# Senior_design_LED_matrix_3_0.net
KiCad netlist of a schematic drawn in Altium Designer
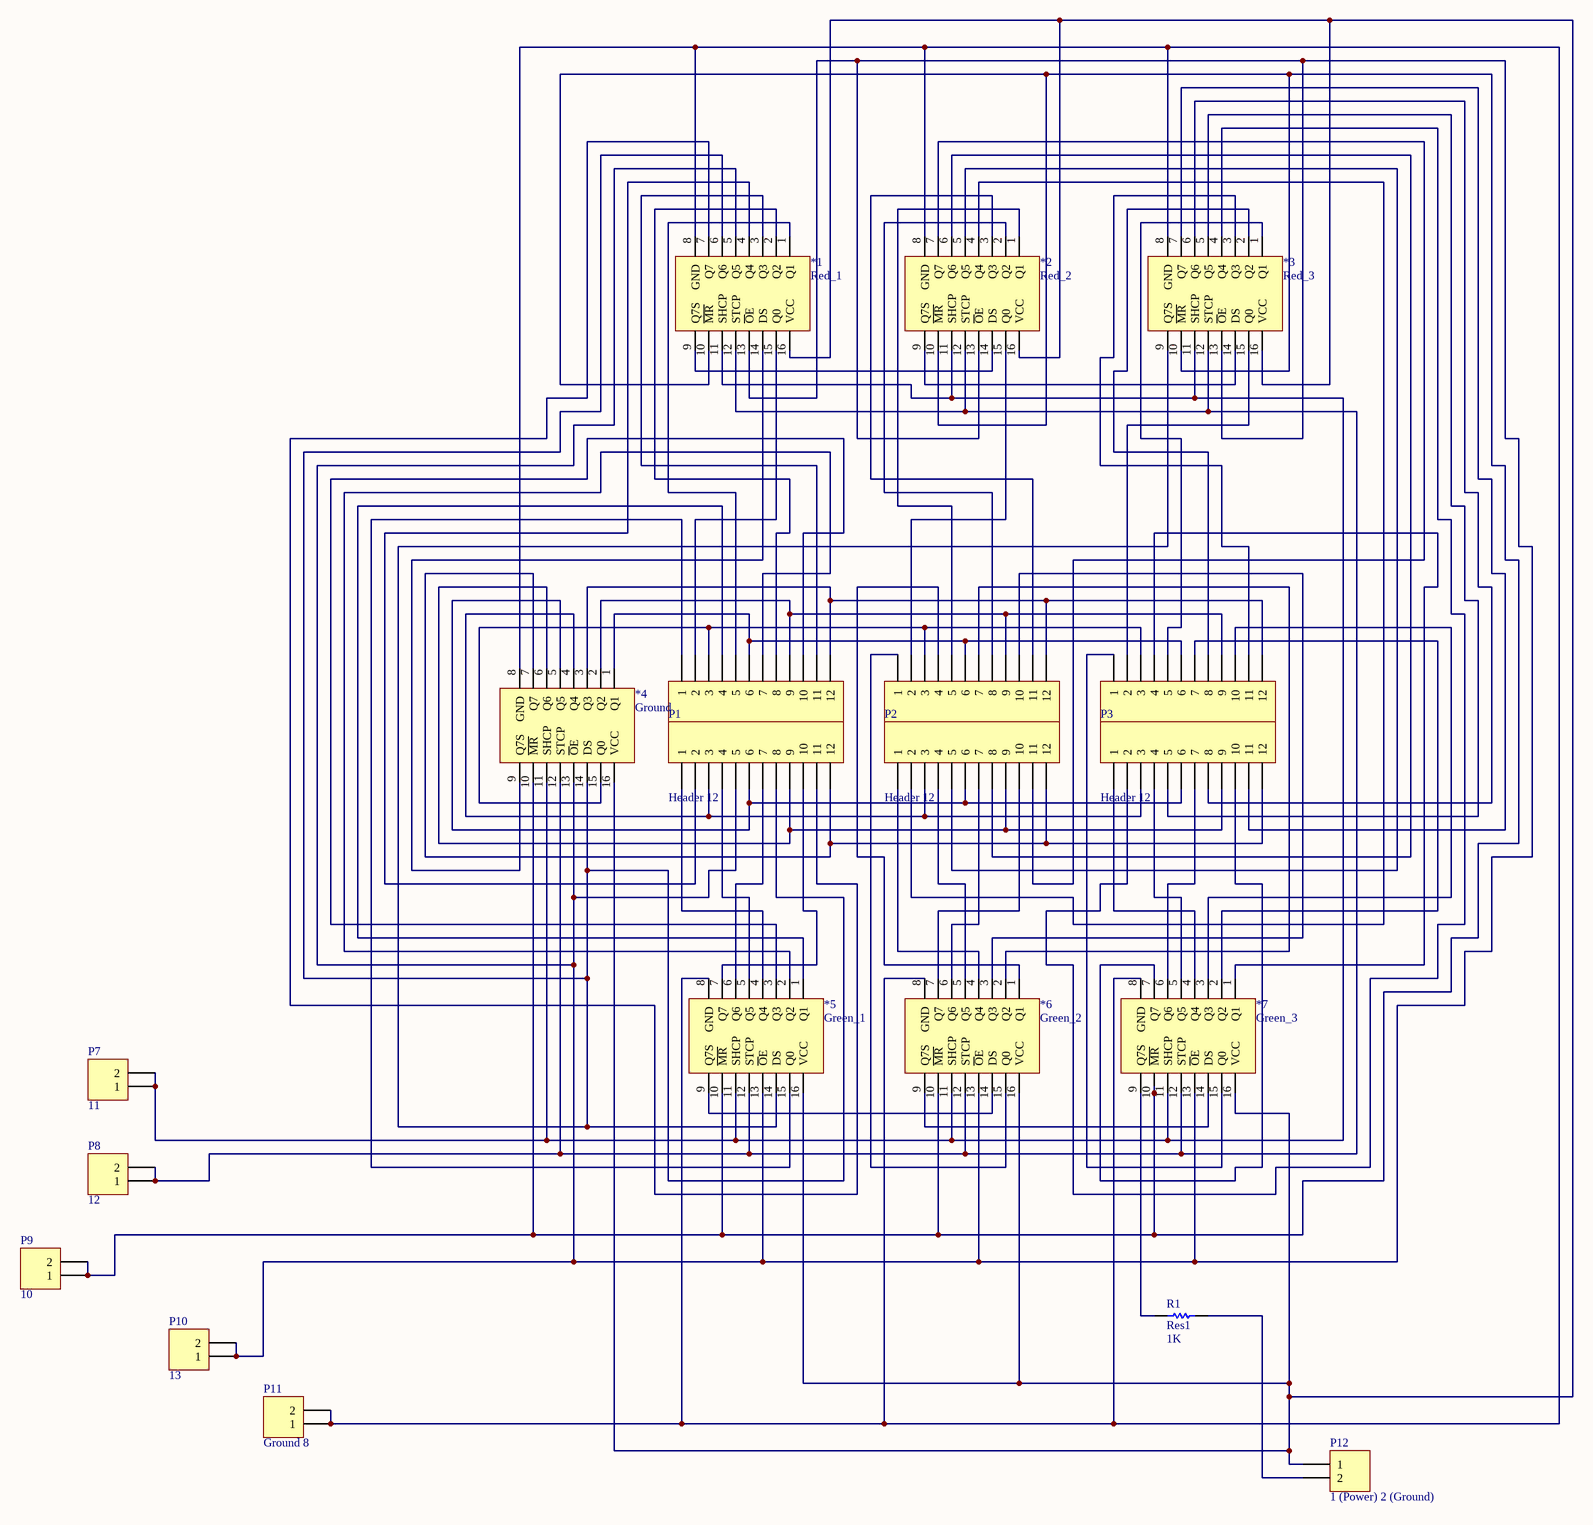
[diagram p0: Senior design LED matrix 3.0.SchDoc]

(export (version "E")
  (design (tool "Eeschema 10.0.6"))
  (components
    (comp (ref "*1") (value "Red_1") (footprint "DIP-16") (libsource (lib "SN74HC595") (part "Component_1")))
    (comp (ref "*2") (value "Red_2") (footprint "DIP-16") (libsource (lib "SN74HC595") (part "Component_1")))
    (comp (ref "*3") (value "Red_3") (footprint "DIP-16") (libsource (lib "SN74HC595") (part "Component_1")))
    (comp (ref "*4") (value "Ground") (footprint "DIP-16") (libsource (lib "SN74HC595") (part "Component_1")))
    (comp (ref "*5")
      (value "Green_1")
      (footprint "DIP-16")
      (libsource (lib "SN74HC595") (part "Component_1"))
    )
    (comp (ref "*6")
      (value "Green_2")
      (footprint "DIP-16")
      (libsource (lib "SN74HC595") (part "Component_1"))
    )
    (comp (ref "*7")
      (value "Green_3")
      (footprint "DIP-16")
      (libsource (lib "SN74HC595") (part "Component_1"))
    )
    (comp (ref "P1")
      (value "Header 12")
      (footprint "HDR1X12")
      (description "Header, 12-Pin")
      (fields (field (name "PUBLISHER") "Altium Limited"))
      (libsource (lib "Miscellaneous Connectors") (part "Header 12"))
    )
    (comp (ref "P2")
      (value "Header 12")
      (footprint "HDR1X12")
      (description "Header, 12-Pin")
      (fields (field (name "PUBLISHER") "Altium Limited"))
      (libsource (lib "Miscellaneous Connectors") (part "Header 12"))
    )
    (comp (ref "P3")
      (value "Header 12")
      (footprint "HDR1X12")
      (description "Header, 12-Pin")
      (fields (field (name "PUBLISHER") "Altium Limited"))
      (libsource (lib "Miscellaneous Connectors") (part "Header 12"))
    )
    (comp (ref "P4")
      (value "Header 12")
      (footprint "HDR1X12")
      (description "Header, 12-Pin")
      (fields (field (name "PUBLISHER") "Altium Limited"))
      (libsource (lib "") (part "Header 12_1"))
    )
    (comp (ref "P5")
      (value "Header 12")
      (footprint "HDR1X12")
      (description "Header, 12-Pin")
      (fields (field (name "PUBLISHER") "Altium Limited"))
      (libsource (lib "") (part "Header 12_1"))
    )
    (comp (ref "P6")
      (value "Header 12")
      (footprint "HDR1X12")
      (description "Header, 12-Pin")
      (fields (field (name "PUBLISHER") "Altium Limited"))
      (libsource (lib "") (part "Header 12_1"))
    )
    (comp (ref "P7")
      (value "11")
      (footprint "HDR1X2")
      (description "Header, 2-Pin")
      (fields (field (name "PUBLISHER") "Altium Limited"))
      (libsource (lib "Miscellaneous Connectors") (part "Header 2"))
    )
    (comp (ref "P8")
      (value "12")
      (footprint "HDR1X2")
      (description "Header, 2-Pin")
      (fields (field (name "PUBLISHER") "Altium Limited"))
      (libsource (lib "Miscellaneous Connectors") (part "Header 2"))
    )
    (comp (ref "P9")
      (value "10")
      (footprint "HDR1X2")
      (description "Header, 2-Pin")
      (fields (field (name "PUBLISHER") "Altium Limited"))
      (libsource (lib "Miscellaneous Connectors") (part "Header 2"))
    )
    (comp (ref "P10")
      (value "13")
      (footprint "HDR1X2")
      (description "Header, 2-Pin")
      (fields (field (name "PUBLISHER") "Altium Limited"))
      (libsource (lib "Miscellaneous Connectors") (part "Header 2"))
    )
    (comp (ref "P11")
      (value "Ground 8")
      (footprint "HDR1X2")
      (description "Header, 2-Pin")
      (fields (field (name "PUBLISHER") "Altium Limited"))
      (libsource (lib "Miscellaneous Connectors") (part "Header 2"))
    )
    (comp (ref "P12")
      (value "1 (Power) 2 (Ground)")
      (footprint "HDR1X2")
      (description "Header, 2-Pin")
      (fields (field (name "PUBLISHER") "Altium Limited"))
      (libsource (lib "") (part "Header 2_1"))
    )
    (comp (ref "R1")
      (value "Res1")
      (footprint "AXIAL-0.3")
      (description "Resistor")
      (fields (field (name "ALTIUM_VALUE") "1K") (field (name "PUBLISHER") "Altium Limited"))
      (libsource (lib "Miscellaneous Devices") (part "Res1"))
    )
  )
  (nets
    (net (code "1") (name "Net-(*1-DS)") (class "Default")
      (node (ref "*1") (pin "14") (pinfunction "DS_14") (pintype "passive"))
      (node (ref "*4") (pin "9") (pinfunction "Q7S_9") (pintype "passive"))
    )
    (net (code "2") (name "Net-(*1-GND)") (class "Default")
      (node (ref "*1") (pin "8") (pinfunction "GND_8") (pintype "passive"))
      (node (ref "*2") (pin "8") (pinfunction "GND_8") (pintype "passive"))
      (node (ref "*3") (pin "8") (pinfunction "GND_8") (pintype "passive"))
      (node (ref "*4") (pin "8") (pinfunction "GND_8") (pintype "passive"))
      (node (ref "*5") (pin "8") (pinfunction "GND_8") (pintype "passive"))
      (node (ref "*6") (pin "8") (pinfunction "GND_8") (pintype "passive"))
      (node (ref "*7") (pin "8") (pinfunction "GND_8") (pintype "passive"))
      (node (ref "P11") (pin "1") (pinfunction "1_1") (pintype "passive"))
      (node (ref "P11") (pin "2") (pinfunction "2_2") (pintype "passive"))
    )
    (net (code "3") (name "Net-(*1-Q0)") (class "Default")
      (node (ref "*1") (pin "15") (pinfunction "Q0_15") (pintype "passive"))
      (node (ref "P4") (pin "2") (pinfunction "2_2") (pintype "passive"))
    )
    (net (code "4") (name "Net-(*1-Q1)") (class "Default")
      (node (ref "*1") (pin "1") (pinfunction "Q1_1") (pintype "passive"))
      (node (ref "P4") (pin "5") (pinfunction "5_5") (pintype "passive"))
    )
    (net (code "5") (name "Net-(*1-Q2)") (class "Default")
      (node (ref "*1") (pin "2") (pinfunction "Q2_2") (pintype "passive"))
      (node (ref "P4") (pin "8") (pinfunction "8_8") (pintype "passive"))
    )
    (net (code "6") (name "Net-(*1-Q3)") (class "Default")
      (node (ref "*1") (pin "3") (pinfunction "Q3_3") (pintype "passive"))
      (node (ref "P4") (pin "11") (pinfunction "11_11") (pintype "passive"))
    )
    (net (code "7") (name "Net-(*1-Q4)") (class "Default")
      (node (ref "*1") (pin "4") (pinfunction "Q4_4") (pintype "passive"))
      (node (ref "P1") (pin "2") (pinfunction "2_2") (pintype "passive"))
    )
    (net (code "8") (name "Net-(*1-Q5)") (class "Default")
      (node (ref "*1") (pin "13") (pinfunction "~{O}E_13") (pintype "passive"))
      (node (ref "*1") (pin "5") (pinfunction "Q5_5") (pintype "passive"))
      (node (ref "*2") (pin "13") (pinfunction "~{O}E_13") (pintype "passive"))
      (node (ref "*3") (pin "13") (pinfunction "~{O}E_13") (pintype "passive"))
      (node (ref "*4") (pin "13") (pinfunction "~{O}E_13") (pintype "passive"))
      (node (ref "*5") (pin "13") (pinfunction "~{O}E_13") (pintype "passive"))
      (node (ref "*6") (pin "13") (pinfunction "~{O}E_13") (pintype "passive"))
      (node (ref "*7") (pin "13") (pinfunction "~{O}E_13") (pintype "passive"))
      (node (ref "P1") (pin "5") (pinfunction "5_5") (pintype "passive"))
      (node (ref "P10") (pin "1") (pinfunction "1_1") (pintype "passive"))
      (node (ref "P10") (pin "2") (pinfunction "2_2") (pintype "passive"))
    )
    (net (code "9") (name "Net-(*1-Q6)") (class "Default")
      (node (ref "*1") (pin "6") (pinfunction "Q6_6") (pintype "passive"))
      (node (ref "*3") (pin "9") (pinfunction "Q7S_9") (pintype "passive"))
      (node (ref "*4") (pin "14") (pinfunction "DS_14") (pintype "passive"))
      (node (ref "*5") (pin "14") (pinfunction "DS_14") (pintype "passive"))
      (node (ref "P1") (pin "8") (pinfunction "8_8") (pintype "passive"))
    )
    (net (code "10") (name "Net-(*1-Q7)") (class "Default")
      (node (ref "*1") (pin "7") (pinfunction "Q7_7") (pintype "passive"))
      (node (ref "P1") (pin "11") (pinfunction "11_11") (pintype "passive"))
    )
    (net (code "11") (name "Net-(*1-Q7S)") (class "Default")
      (node (ref "*1") (pin "9") (pinfunction "Q7S_9") (pintype "passive"))
      (node (ref "*2") (pin "14") (pinfunction "DS_14") (pintype "passive"))
    )
    (net (code "12") (name "Net-(*1-SHCP)") (class "Default")
      (node (ref "*1") (pin "11") (pinfunction "SHCP_11") (pintype "passive"))
      (node (ref "*2") (pin "11") (pinfunction "SHCP_11") (pintype "passive"))
      (node (ref "*3") (pin "11") (pinfunction "SHCP_11") (pintype "passive"))
      (node (ref "*4") (pin "11") (pinfunction "SHCP_11") (pintype "passive"))
      (node (ref "*5") (pin "11") (pinfunction "SHCP_11") (pintype "passive"))
      (node (ref "*6") (pin "11") (pinfunction "SHCP_11") (pintype "passive"))
      (node (ref "*7") (pin "11") (pinfunction "SHCP_11") (pintype "passive"))
      (node (ref "P7") (pin "1") (pinfunction "1_1") (pintype "passive"))
      (node (ref "P7") (pin "2") (pinfunction "2_2") (pintype "passive"))
    )
    (net (code "13") (name "Net-(*1-STCP)") (class "Default")
      (node (ref "*1") (pin "12") (pinfunction "STCP_12") (pintype "passive"))
      (node (ref "*2") (pin "12") (pinfunction "STCP_12") (pintype "passive"))
      (node (ref "*3") (pin "12") (pinfunction "STCP_12") (pintype "passive"))
      (node (ref "*4") (pin "12") (pinfunction "STCP_12") (pintype "passive"))
      (node (ref "*5") (pin "12") (pinfunction "STCP_12") (pintype "passive"))
      (node (ref "*6") (pin "12") (pinfunction "STCP_12") (pintype "passive"))
      (node (ref "*7") (pin "12") (pinfunction "STCP_12") (pintype "passive"))
      (node (ref "P8") (pin "1") (pinfunction "1_1") (pintype "passive"))
      (node (ref "P8") (pin "2") (pinfunction "2_2") (pintype "passive"))
    )
    (net (code "14") (name "Net-(*1-VCC)") (class "Default")
      (node (ref "*1") (pin "16") (pinfunction "VCC_16") (pintype "passive"))
      (node (ref "*2") (pin "16") (pinfunction "VCC_16") (pintype "passive"))
      (node (ref "*3") (pin "16") (pinfunction "VCC_16") (pintype "passive"))
      (node (ref "*4") (pin "16") (pinfunction "VCC_16") (pintype "passive"))
      (node (ref "*5") (pin "16") (pinfunction "VCC_16") (pintype "passive"))
      (node (ref "*6") (pin "16") (pinfunction "VCC_16") (pintype "passive"))
      (node (ref "*7") (pin "16") (pinfunction "VCC_16") (pintype "passive"))
      (node (ref "P12") (pin "1") (pinfunction "1_1") (pintype "passive"))
    )
    (net (code "15") (name "Net-(*1-~{MR})") (class "Default")
      (node (ref "*1") (pin "10") (pinfunction "~{MR}_10") (pintype "passive"))
      (node (ref "*2") (pin "10") (pinfunction "~{MR}_10") (pintype "passive"))
      (node (ref "*3") (pin "10") (pinfunction "~{MR}_10") (pintype "passive"))
      (node (ref "*4") (pin "10") (pinfunction "~{MR}_10") (pintype "passive"))
      (node (ref "*5") (pin "10") (pinfunction "~{MR}_10") (pintype "passive"))
      (node (ref "*6") (pin "10") (pinfunction "~{MR}_10") (pintype "passive"))
      (node (ref "*7") (pin "10") (pinfunction "~{MR}_10") (pintype "passive"))
      (node (ref "P9") (pin "1") (pinfunction "1_1") (pintype "passive"))
      (node (ref "P9") (pin "2") (pinfunction "2_2") (pintype "passive"))
    )
    (net (code "16") (name "Net-(*2-Q0)") (class "Default")
      (node (ref "*2") (pin "15") (pinfunction "Q0_15") (pintype "passive"))
      (node (ref "P5") (pin "2") (pinfunction "2_2") (pintype "passive"))
    )
    (net (code "17") (name "Net-(*2-Q1)") (class "Default")
      (node (ref "*2") (pin "1") (pinfunction "Q1_1") (pintype "passive"))
      (node (ref "P5") (pin "5") (pinfunction "5_5") (pintype "passive"))
    )
    (net (code "18") (name "Net-(*2-Q2)") (class "Default")
      (node (ref "*2") (pin "2") (pinfunction "Q2_2") (pintype "passive"))
      (node (ref "P5") (pin "8") (pinfunction "8_8") (pintype "passive"))
    )
    (net (code "19") (name "Net-(*2-Q3)") (class "Default")
      (node (ref "*2") (pin "3") (pinfunction "Q3_3") (pintype "passive"))
      (node (ref "P5") (pin "11") (pinfunction "11_11") (pintype "passive"))
    )
    (net (code "20") (name "Net-(*2-Q4)") (class "Default")
      (node (ref "*2") (pin "4") (pinfunction "Q4_4") (pintype "passive"))
      (node (ref "P2") (pin "2") (pinfunction "2_2") (pintype "passive"))
    )
    (net (code "21") (name "Net-(*2-Q5)") (class "Default")
      (node (ref "*2") (pin "5") (pinfunction "Q5_5") (pintype "passive"))
      (node (ref "P2") (pin "5") (pinfunction "5_5") (pintype "passive"))
    )
    (net (code "22") (name "Net-(*2-Q6)") (class "Default")
      (node (ref "*2") (pin "6") (pinfunction "Q6_6") (pintype "passive"))
      (node (ref "P2") (pin "8") (pinfunction "8_8") (pintype "passive"))
    )
    (net (code "23") (name "Net-(*2-Q7)") (class "Default")
      (node (ref "*2") (pin "7") (pinfunction "Q7_7") (pintype "passive"))
      (node (ref "P2") (pin "11") (pinfunction "11_11") (pintype "passive"))
    )
    (net (code "24") (name "Net-(*2-Q7S)") (class "Default")
      (node (ref "*2") (pin "9") (pinfunction "Q7S_9") (pintype "passive"))
      (node (ref "*3") (pin "14") (pinfunction "DS_14") (pintype "passive"))
    )
    (net (code "25") (name "Net-(*3-Q0)") (class "Default")
      (node (ref "*3") (pin "15") (pinfunction "Q0_15") (pintype "passive"))
      (node (ref "P6") (pin "2") (pinfunction "2_2") (pintype "passive"))
    )
    (net (code "26") (name "Net-(*3-Q1)") (class "Default")
      (node (ref "*3") (pin "1") (pinfunction "Q1_1") (pintype "passive"))
      (node (ref "P6") (pin "5") (pinfunction "5_5") (pintype "passive"))
    )
    (net (code "27") (name "Net-(*3-Q2)") (class "Default")
      (node (ref "*3") (pin "2") (pinfunction "Q2_2") (pintype "passive"))
      (node (ref "P6") (pin "8") (pinfunction "8_8") (pintype "passive"))
    )
    (net (code "28") (name "Net-(*3-Q3)") (class "Default")
      (node (ref "*3") (pin "3") (pinfunction "Q3_3") (pintype "passive"))
      (node (ref "P6") (pin "11") (pinfunction "11_11") (pintype "passive"))
    )
    (net (code "29") (name "Net-(*3-Q4)") (class "Default")
      (node (ref "*3") (pin "4") (pinfunction "Q4_4") (pintype "passive"))
      (node (ref "P3") (pin "2") (pinfunction "2_2") (pintype "passive"))
    )
    (net (code "30") (name "Net-(*3-Q5)") (class "Default")
      (node (ref "*3") (pin "5") (pinfunction "Q5_5") (pintype "passive"))
      (node (ref "P3") (pin "5") (pinfunction "5_5") (pintype "passive"))
    )
    (net (code "31") (name "Net-(*3-Q6)") (class "Default")
      (node (ref "*3") (pin "6") (pinfunction "Q6_6") (pintype "passive"))
      (node (ref "P3") (pin "8") (pinfunction "8_8") (pintype "passive"))
    )
    (net (code "32") (name "Net-(*3-Q7)") (class "Default")
      (node (ref "*3") (pin "7") (pinfunction "Q7_7") (pintype "passive"))
      (node (ref "P3") (pin "11") (pinfunction "11_11") (pintype "passive"))
    )
    (net (code "33") (name "Net-(*4-Q0)") (class "Default")
      (node (ref "*4") (pin "15") (pinfunction "Q0_15") (pintype "passive"))
      (node (ref "P4") (pin "3") (pinfunction "3_3") (pintype "passive"))
      (node (ref "P5") (pin "3") (pinfunction "3_3") (pintype "passive"))
      (node (ref "P6") (pin "3") (pinfunction "3_3") (pintype "passive"))
    )
    (net (code "34") (name "Net-(*4-Q1)") (class "Default")
      (node (ref "*4") (pin "1") (pinfunction "Q1_1") (pintype "passive"))
      (node (ref "P4") (pin "6") (pinfunction "6_6") (pintype "passive"))
      (node (ref "P5") (pin "6") (pinfunction "6_6") (pintype "passive"))
      (node (ref "P6") (pin "6") (pinfunction "6_6") (pintype "passive"))
    )
    (net (code "35") (name "Net-(*4-Q2)") (class "Default")
      (node (ref "*4") (pin "2") (pinfunction "Q2_2") (pintype "passive"))
      (node (ref "P4") (pin "9") (pinfunction "9_9") (pintype "passive"))
      (node (ref "P5") (pin "9") (pinfunction "9_9") (pintype "passive"))
      (node (ref "P6") (pin "9") (pinfunction "9_9") (pintype "passive"))
    )
    (net (code "36") (name "Net-(*4-Q3)") (class "Default")
      (node (ref "*4") (pin "3") (pinfunction "Q3_3") (pintype "passive"))
      (node (ref "P4") (pin "12") (pinfunction "12_12") (pintype "passive"))
      (node (ref "P5") (pin "12") (pinfunction "12_12") (pintype "passive"))
      (node (ref "P6") (pin "12") (pinfunction "12_12") (pintype "passive"))
    )
    (net (code "37") (name "Net-(*4-Q4)") (class "Default")
      (node (ref "*4") (pin "4") (pinfunction "Q4_4") (pintype "passive"))
      (node (ref "P1") (pin "3") (pinfunction "3_3") (pintype "passive"))
      (node (ref "P2") (pin "3") (pinfunction "3_3") (pintype "passive"))
      (node (ref "P3") (pin "3") (pinfunction "3_3") (pintype "passive"))
    )
    (net (code "38") (name "Net-(*4-Q5)") (class "Default")
      (node (ref "*4") (pin "5") (pinfunction "Q5_5") (pintype "passive"))
      (node (ref "P1") (pin "6") (pinfunction "6_6") (pintype "passive"))
      (node (ref "P2") (pin "6") (pinfunction "6_6") (pintype "passive"))
      (node (ref "P3") (pin "6") (pinfunction "6_6") (pintype "passive"))
    )
    (net (code "39") (name "Net-(*4-Q6)") (class "Default")
      (node (ref "*4") (pin "6") (pinfunction "Q6_6") (pintype "passive"))
      (node (ref "P1") (pin "9") (pinfunction "9_9") (pintype "passive"))
      (node (ref "P2") (pin "9") (pinfunction "9_9") (pintype "passive"))
      (node (ref "P3") (pin "9") (pinfunction "9_9") (pintype "passive"))
    )
    (net (code "40") (name "Net-(*4-Q7)") (class "Default")
      (node (ref "*4") (pin "7") (pinfunction "Q7_7") (pintype "passive"))
      (node (ref "P1") (pin "12") (pinfunction "12_12") (pintype "passive"))
      (node (ref "P2") (pin "12") (pinfunction "12_12") (pintype "passive"))
      (node (ref "P3") (pin "12") (pinfunction "12_12") (pintype "passive"))
    )
    (net (code "41") (name "Net-(*5-Q0)") (class "Default")
      (node (ref "*5") (pin "15") (pinfunction "Q0_15") (pintype "passive"))
      (node (ref "P4") (pin "1") (pinfunction "1_1") (pintype "passive"))
    )
    (net (code "42") (name "Net-(*5-Q1)") (class "Default")
      (node (ref "*5") (pin "1") (pinfunction "Q1_1") (pintype "passive"))
      (node (ref "P4") (pin "4") (pinfunction "4_4") (pintype "passive"))
    )
    (net (code "43") (name "Net-(*5-Q2)") (class "Default")
      (node (ref "*5") (pin "2") (pinfunction "Q2_2") (pintype "passive"))
      (node (ref "P4") (pin "7") (pinfunction "7_7") (pintype "passive"))
    )
    (net (code "44") (name "Net-(*5-Q3)") (class "Default")
      (node (ref "*5") (pin "3") (pinfunction "Q3_3") (pintype "passive"))
      (node (ref "P4") (pin "10") (pinfunction "10_10") (pintype "passive"))
    )
    (net (code "45") (name "Net-(*5-Q4)") (class "Default")
      (node (ref "*5") (pin "4") (pinfunction "Q4_4") (pintype "passive"))
      (node (ref "P1") (pin "1") (pinfunction "1_1") (pintype "passive"))
    )
    (net (code "46") (name "Net-(*5-Q5)") (class "Default")
      (node (ref "*5") (pin "5") (pinfunction "Q5_5") (pintype "passive"))
      (node (ref "P1") (pin "4") (pinfunction "4_4") (pintype "passive"))
    )
    (net (code "47") (name "Net-(*5-Q6)") (class "Default")
      (node (ref "*5") (pin "6") (pinfunction "Q6_6") (pintype "passive"))
      (node (ref "P1") (pin "7") (pinfunction "7_7") (pintype "passive"))
    )
    (net (code "48") (name "Net-(*5-Q7)") (class "Default")
      (node (ref "*5") (pin "7") (pinfunction "Q7_7") (pintype "passive"))
      (node (ref "P1") (pin "10") (pinfunction "10_10") (pintype "passive"))
    )
    (net (code "49") (name "Net-(*5-Q7S)") (class "Default")
      (node (ref "*5") (pin "9") (pinfunction "Q7S_9") (pintype "passive"))
      (node (ref "*6") (pin "14") (pinfunction "DS_14") (pintype "passive"))
    )
    (net (code "50") (name "Net-(*6-Q0)") (class "Default")
      (node (ref "*6") (pin "15") (pinfunction "Q0_15") (pintype "passive"))
      (node (ref "P5") (pin "1") (pinfunction "1_1") (pintype "passive"))
    )
    (net (code "51") (name "Net-(*6-Q1)") (class "Default")
      (node (ref "*6") (pin "1") (pinfunction "Q1_1") (pintype "passive"))
      (node (ref "P5") (pin "4") (pinfunction "4_4") (pintype "passive"))
    )
    (net (code "52") (name "Net-(*6-Q2)") (class "Default")
      (node (ref "*6") (pin "2") (pinfunction "Q2_2") (pintype "passive"))
      (node (ref "P5") (pin "7") (pinfunction "7_7") (pintype "passive"))
    )
    (net (code "53") (name "Net-(*6-Q3)") (class "Default")
      (node (ref "*6") (pin "3") (pinfunction "Q3_3") (pintype "passive"))
      (node (ref "P5") (pin "10") (pinfunction "10_10") (pintype "passive"))
    )
    (net (code "54") (name "Net-(*6-Q4)") (class "Default")
      (node (ref "*6") (pin "4") (pinfunction "Q4_4") (pintype "passive"))
      (node (ref "P2") (pin "1") (pinfunction "1_1") (pintype "passive"))
    )
    (net (code "55") (name "Net-(*6-Q5)") (class "Default")
      (node (ref "*6") (pin "5") (pinfunction "Q5_5") (pintype "passive"))
      (node (ref "P2") (pin "4") (pinfunction "4_4") (pintype "passive"))
    )
    (net (code "56") (name "Net-(*6-Q6)") (class "Default")
      (node (ref "*6") (pin "6") (pinfunction "Q6_6") (pintype "passive"))
      (node (ref "P2") (pin "7") (pinfunction "7_7") (pintype "passive"))
    )
    (net (code "57") (name "Net-(*6-Q7)") (class "Default")
      (node (ref "*6") (pin "7") (pinfunction "Q7_7") (pintype "passive"))
      (node (ref "P2") (pin "10") (pinfunction "10_10") (pintype "passive"))
    )
    (net (code "58") (name "Net-(*6-Q7S)") (class "Default")
      (node (ref "*6") (pin "9") (pinfunction "Q7S_9") (pintype "passive"))
      (node (ref "*7") (pin "14") (pinfunction "DS_14") (pintype "passive"))
    )
    (net (code "59") (name "Net-(*7-Q0)") (class "Default")
      (node (ref "*7") (pin "15") (pinfunction "Q0_15") (pintype "passive"))
      (node (ref "P6") (pin "1") (pinfunction "1_1") (pintype "passive"))
    )
    (net (code "60") (name "Net-(*7-Q1)") (class "Default")
      (node (ref "*7") (pin "1") (pinfunction "Q1_1") (pintype "passive"))
      (node (ref "P6") (pin "4") (pinfunction "4_4") (pintype "passive"))
    )
    (net (code "61") (name "Net-(*7-Q2)") (class "Default")
      (node (ref "*7") (pin "2") (pinfunction "Q2_2") (pintype "passive"))
      (node (ref "P6") (pin "7") (pinfunction "7_7") (pintype "passive"))
    )
    (net (code "62") (name "Net-(*7-Q3)") (class "Default")
      (node (ref "*7") (pin "3") (pinfunction "Q3_3") (pintype "passive"))
      (node (ref "P6") (pin "10") (pinfunction "10_10") (pintype "passive"))
    )
    (net (code "63") (name "Net-(*7-Q4)") (class "Default")
      (node (ref "*7") (pin "4") (pinfunction "Q4_4") (pintype "passive"))
      (node (ref "P3") (pin "1") (pinfunction "1_1") (pintype "passive"))
    )
    (net (code "64") (name "Net-(*7-Q5)") (class "Default")
      (node (ref "*7") (pin "5") (pinfunction "Q5_5") (pintype "passive"))
      (node (ref "P3") (pin "4") (pinfunction "4_4") (pintype "passive"))
    )
    (net (code "65") (name "Net-(*7-Q6)") (class "Default")
      (node (ref "*7") (pin "6") (pinfunction "Q6_6") (pintype "passive"))
      (node (ref "P3") (pin "7") (pinfunction "7_7") (pintype "passive"))
    )
    (net (code "66") (name "Net-(*7-Q7)") (class "Default")
      (node (ref "*7") (pin "7") (pinfunction "Q7_7") (pintype "passive"))
      (node (ref "P3") (pin "10") (pinfunction "10_10") (pintype "passive"))
    )
    (net (code "67") (name "Net-(*7-Q7S)") (class "Default")
      (node (ref "*7") (pin "9") (pinfunction "Q7S_9") (pintype "passive"))
      (node (ref "R1") (pin "1") (pinfunction "1_1") (pintype "passive"))
    )
    (net (code "68") (name "Net-(P12-Pad2)") (class "Default")
      (node (ref "P12") (pin "2") (pinfunction "2_2") (pintype "passive"))
      (node (ref "R1") (pin "2") (pinfunction "2_2") (pintype "passive"))
    )
  )
)
